# EUP3489.net
KiCad netlist of a schematic drawn in Altium Designer
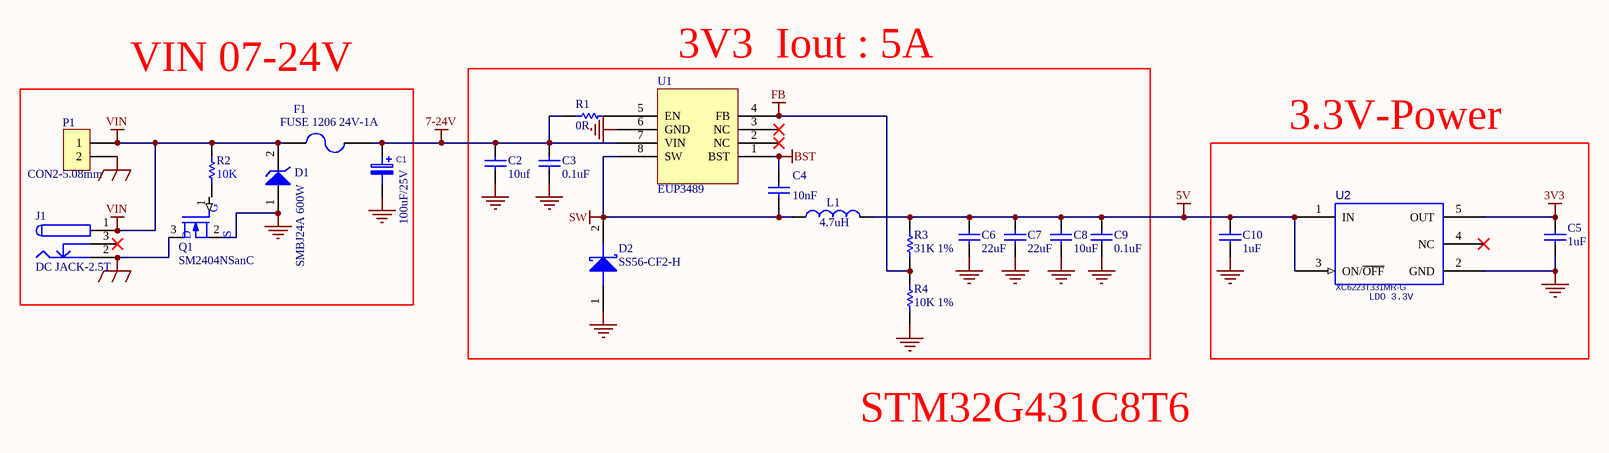
[diagram p0: EUP3489.SchDoc]

(export (version "E")
  (design (tool "Eeschema 10.0.6"))
  (components
    (comp (ref "C1")
      (value "100uF/25V")
      (footprint "DIP CAP-8*3.5")
      (fields (field (name "PART NUMBER") "53300833000") (field (name "TOLERANCE") "20%"))
      (libsource (lib "*") (part "C POL"))
    )
    (comp (ref "C2")
      (value "10uf")
      (footprint "0603C")
      (description "Capacitor")
      (fields (field (name "PUBLISHER") "Altium Limited"))
      (libsource (lib "*") (part "Cap Semi"))
    )
    (comp (ref "C3")
      (value "0.1uF")
      (footprint "0603C")
      (description "Capacitor (Semiconductor SIM Model)")
      (fields (field (name "PUBLISHER") "Altium Limited"))
      (libsource (lib "*") (part "Cap Semi"))
    )
    (comp (ref "C4")
      (value "10nF")
      (footprint "0603C")
      (description "Capacitor (Semiconductor SIM Model)")
      (fields (field (name "PUBLISHER") "Altium Limited"))
      (libsource (lib "*") (part "Cap Semi"))
    )
    (comp (ref "C5")
      (value "1uF")
      (footprint "0603C")
      (description "Capacitor (Semiconductor SIM Model)")
      (fields (field (name "PUBLISHER") "Altium Limited"))
      (libsource (lib "*") (part "Cap Semi"))
    )
    (comp (ref "C6")
      (value "22uF")
      (footprint "0805C")
      (description "Capacitor")
      (libsource (lib "*") (part "Cap Semi"))
    )
    (comp (ref "C7")
      (value "22uF")
      (footprint "0805C")
      (description "Capacitor")
      (libsource (lib "*") (part "Cap Semi"))
    )
    (comp (ref "C8")
      (value "10uF")
      (footprint "0603C")
      (description "Capacitor")
      (libsource (lib "*") (part "Cap Semi"))
    )
    (comp (ref "C9")
      (value "0.1uF")
      (footprint "0603C")
      (description "Capacitor")
      (libsource (lib "*") (part "Cap Semi"))
    )
    (comp (ref "C10")
      (value "1uF")
      (footprint "0603C")
      (description "Capacitor (Semiconductor SIM Model)")
      (fields (field (name "PUBLISHER") "Altium Limited"))
      (libsource (lib "*") (part "Cap Semi"))
    )
    (comp (ref "D1")
      (value "SMBJ24A 600W")
      (footprint "SMBJ40CA(TVS)")
      (description "Zener Diode")
      (libsource (lib "*") (part "PESD5V0L1BA"))
    )
    (comp (ref "D2")
      (value "SS56-CF2-H")
      (footprint "SS56-CF2-H")
      (description "Schottky Diode")
      (libsource (lib "*") (part "DIODE SCHOTTKY"))
    )
    (comp (ref "F1")
      (value "FUSE 1206 24V-1A")
      (footprint "1206-FUSE")
      (description "Fuse")
      (libsource (lib "*") (part "FUSE2"))
    )
    (comp (ref "J1")
      (value "DC JACK-2.5T")
      (footprint "DC JACK-2.5T-NEW")
      (description "Low Voltage Power Supply Connector")
      (fields (field (name "PUBLISHER") "*"))
      (libsource (lib "*") (part "DCJACK-1"))
    )
    (comp (ref "L1")
      (value "4.7uH")
      (footprint "L7X6.6")
      (description "Inductor")
      (fields (field (name "PUBLISHER") "Altium Limited"))
      (libsource (lib "*") (part "Inductor"))
    )
    (comp (ref "P1")
      (value "CON2-5.08mm")
      (footprint "OQ5.08-90D-2P")
      (description "Connector")
      (libsource (lib "*") (part "CON2"))
    )
    (comp (ref "Q1")
      (value "SM2404NSanC")
      (footprint "SOT-23")
      (description "N-Channel Mosfet")
      (libsource (lib "*") (part "MOSFET N-1"))
    )
    (comp (ref "R1")
      (value "0R")
      (footprint "0603")
      (description "Semiconductor Resistor")
      (fields (field (name "PUBLISHER") "Altium Limited"))
      (libsource (lib "*") (part "Res Semi"))
    )
    (comp (ref "R2")
      (value "10K")
      (footprint "0603")
      (description "Semiconductor Resistor")
      (fields (field (name "PUBLISHER") "Altium Limited"))
      (libsource (lib "*") (part "Res Semi"))
    )
    (comp (ref "R3")
      (value "31K 1%")
      (footprint "0603")
      (description "Semiconductor Resistor")
      (fields (field (name "PUBLISHER") "Altium Limited"))
      (libsource (lib "*") (part "Res Semi"))
    )
    (comp (ref "R4")
      (value "10K 1%")
      (footprint "0603")
      (description "Semiconductor Resistor")
      (fields (field (name "PUBLISHER") "Altium Limited"))
      (libsource (lib "*") (part "Res Semi"))
    )
    (comp (ref "U1")
      (value "EUP3489")
      (footprint "MOS SOP8")
      (description "DC-DC  Buck 5A,30V")
      (libsource (lib "*") (part "EUP3489"))
    )
    (comp (ref "U2")
      (value "XC6223T331MR-G")
      (footprint "SOT-23-5-0.95MM")
      (libsource (lib "*") (part "XC6223T331MR-G"))
    )
  )
  (nets
    (net (code "1") (name "3V3") (class "Default")
      (node (ref "C5") (pin "2") (pinfunction "2_2") (pintype "passive"))
      (node (ref "U2") (pin "5") (pinfunction "OUT_5") (pintype "passive"))
    )
    (net (code "2") (name "5V") (class "Default")
      (node (ref "C10") (pin "2") (pinfunction "2_2") (pintype "passive"))
      (node (ref "C6") (pin "2") (pinfunction "2_2") (pintype "passive"))
      (node (ref "C7") (pin "2") (pinfunction "2_2") (pintype "passive"))
      (node (ref "C8") (pin "2") (pinfunction "2_2") (pintype "passive"))
      (node (ref "C9") (pin "2") (pinfunction "2_2") (pintype "passive"))
      (node (ref "L1") (pin "2") (pinfunction "2_2") (pintype "passive"))
      (node (ref "R3") (pin "2") (pinfunction "2_2") (pintype "passive"))
      (node (ref "U2") (pin "1") (pinfunction "IN_1") (pintype "passive"))
      (node (ref "U2") (pin "3") (pinfunction "ON/~{OFF}_3") (pintype "input"))
    )
    (net (code "3") (name "7-24V") (class "Default")
      (node (ref "C1") (pin "1") (pinfunction "1_1") (pintype "passive"))
      (node (ref "C2") (pin "2") (pinfunction "2_2") (pintype "passive"))
      (node (ref "C3") (pin "2") (pinfunction "2_2") (pintype "passive"))
      (node (ref "F1") (pin "2") (pinfunction "2_2") (pintype "passive"))
      (node (ref "R1") (pin "1") (pinfunction "1_1") (pintype "passive"))
      (node (ref "U1") (pin "7") (pinfunction "VIN_7") (pintype "passive"))
    )
    (net (code "4") (name "BST") (class "Default")
      (node (ref "C4") (pin "1") (pinfunction "1_1") (pintype "passive"))
      (node (ref "U1") (pin "1") (pinfunction "BST_1") (pintype "passive"))
    )
    (net (code "5") (name "FB") (class "Default")
      (node (ref "R3") (pin "1") (pinfunction "1_1") (pintype "passive"))
      (node (ref "R4") (pin "2") (pinfunction "2_2") (pintype "passive"))
      (node (ref "U1") (pin "4") (pinfunction "FB_4") (pintype "passive"))
    )
    (net (code "6") (name "GND") (class "Default")
      (node (ref "C1") (pin "2") (pinfunction "2_2") (pintype "passive"))
      (node (ref "C10") (pin "1") (pinfunction "1_1") (pintype "passive"))
      (node (ref "C2") (pin "1") (pinfunction "1_1") (pintype "passive"))
      (node (ref "C3") (pin "1") (pinfunction "1_1") (pintype "passive"))
      (node (ref "C5") (pin "1") (pinfunction "1_1") (pintype "passive"))
      (node (ref "C6") (pin "1") (pinfunction "1_1") (pintype "passive"))
      (node (ref "C7") (pin "1") (pinfunction "1_1") (pintype "passive"))
      (node (ref "C8") (pin "1") (pinfunction "1_1") (pintype "passive"))
      (node (ref "C9") (pin "1") (pinfunction "1_1") (pintype "passive"))
      (node (ref "D1") (pin "1") (pinfunction "1_1") (pintype "passive"))
      (node (ref "D2") (pin "1") (pinfunction "1_1") (pintype "passive"))
      (node (ref "Q1") (pin "2") (pinfunction "SOURCE_2") (pintype "passive"))
      (node (ref "R4") (pin "1") (pinfunction "1_1") (pintype "passive"))
      (node (ref "U1") (pin "6") (pinfunction "GND_6") (pintype "passive"))
      (node (ref "U2") (pin "2") (pinfunction "GND_2") (pintype "passive"))
    )
    (net (code "7") (name "Net-(U1-EN)") (class "Default")
      (node (ref "R1") (pin "2") (pinfunction "2_2") (pintype "passive"))
      (node (ref "U1") (pin "5") (pinfunction "EN_5") (pintype "passive"))
    )
    (net (code "8") (name "PGND") (class "Default")
      (node (ref "J1") (pin "2") (pinfunction "2_2") (pintype "power_in"))
      (node (ref "P1") (pin "2") (pinfunction "2_2") (pintype "passive"))
      (node (ref "Q1") (pin "3") (pinfunction "DRAIN_3") (pintype "passive"))
    )
    (net (code "9") (name "SW") (class "Default")
      (node (ref "C4") (pin "2") (pinfunction "2_2") (pintype "passive"))
      (node (ref "D2") (pin "2") (pinfunction "2_2") (pintype "passive"))
      (node (ref "L1") (pin "1") (pinfunction "1_1") (pintype "passive"))
      (node (ref "U1") (pin "8") (pinfunction "SW_8") (pintype "passive"))
    )
    (net (code "10") (name "VIN") (class "Default")
      (node (ref "D1") (pin "2") (pinfunction "2_2") (pintype "passive"))
      (node (ref "F1") (pin "1") (pinfunction "1_1") (pintype "passive"))
      (node (ref "J1") (pin "1") (pinfunction "1_1") (pintype "power_in"))
      (node (ref "P1") (pin "1") (pinfunction "1_1") (pintype "passive"))
      (node (ref "R2") (pin "2") (pinfunction "2_2") (pintype "passive"))
    )
    (net (code "11") (name "unconnected-(J1-Pad3)") (class "Default")
      (node (ref "J1") (pin "3") (pinfunction "3_3") (pintype "power_in+no_connect"))
    )
    (net (code "12") (name "unconnected-(Q1-GATE-Pad1)") (class "Default")
      (node (ref "Q1") (pin "1") (pinfunction "GATE_1") (pintype "input"))
    )
    (net (code "13") (name "unconnected-(R2-Pad1)") (class "Default")
      (node (ref "R2") (pin "1") (pinfunction "1_1") (pintype "passive"))
    )
    (net (code "14") (name "unconnected-(U1-NC-Pad2)") (class "Default")
      (node (ref "U1") (pin "2") (pinfunction "NC_2") (pintype "passive+no_connect"))
    )
    (net (code "15") (name "unconnected-(U1-NC-Pad3)") (class "Default")
      (node (ref "U1") (pin "3") (pinfunction "NC_3") (pintype "passive+no_connect"))
    )
    (net (code "16") (name "unconnected-(U2-NC-Pad4)") (class "Default")
      (node (ref "U2") (pin "4") (pinfunction "NC_4") (pintype "passive+no_connect"))
    )
  )
)
